# CONECTORES.net
KiCad netlist of a schematic drawn in Altium Designer
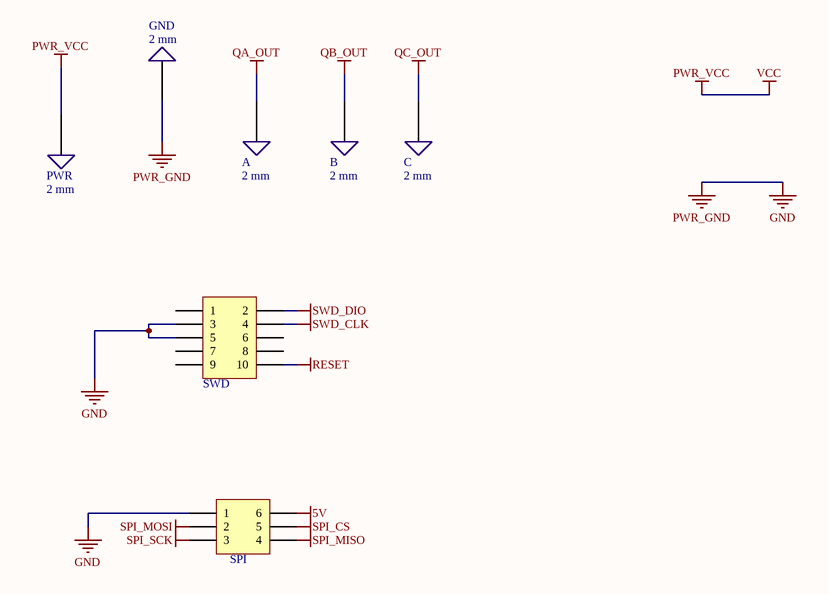
[diagram p0: CONECTORES.SchDoc]

(export (version "E")
  (design (tool "Eeschema 10.0.6"))
  (components
    (comp (ref "A")
      (value "2 mm")
      (footprint "HOLE_2mm")
      (description "Pad to solder wire")
      (libsource (lib "Connector#csv") (part "SOLDERED_WIRE_2mm"))
    )
    (comp (ref "B")
      (value "2 mm")
      (footprint "HOLE_2mm")
      (description "Pad to solder wire")
      (libsource (lib "Connector#csv") (part "SOLDERED_WIRE_2mm"))
    )
    (comp (ref "C")
      (value "2 mm")
      (footprint "HOLE_2mm")
      (description "Pad to solder wire")
      (libsource (lib "Connector#csv") (part "SOLDERED_WIRE_2mm"))
    )
    (comp (ref "GND")
      (value "2 mm")
      (footprint "HOLE_2mm")
      (description "Pad to solder wire")
      (libsource (lib "Connector#csv") (part "SOLDERED_WIRE_2mm"))
    )
    (comp (ref "PWR")
      (value "2 mm")
      (footprint "HOLE_2mm")
      (description "Pad to solder wire")
      (libsource (lib "Connector#csv") (part "SOLDERED_WIRE_2mm"))
    )
    (comp (ref "SPI")
      (value "Header 3X2")
      (footprint "Pines 2X3")
      (description "Header, 3-Pin, Dual row")
      (fields (field (name "PUBLISHER") "Altium Limited"))
      (libsource (lib "ConnectorsGordo") (part "Header 3X2"))
    )
    (comp (ref "SWD")
      (value "HEADER-5x2S")
      (footprint "G-HEADER_5x2I.05P_SM")
      (description "CONN HEADER 10POS DL UNSHRD SMD")
      (libsource (lib "Connector#csv") (part "HEADER_5x2_50mil_U"))
    )
  )
  (nets
    (net (code "1") (name "5V") (class "Default")
      (node (ref "SPI") (pin "6") (pinfunction "6_6") (pintype "passive"))
    )
    (net (code "2") (name "GND") (class "Default")
      (node (ref "GND") (pin "1") (pinfunction "Wire_1") (pintype "passive"))
      (node (ref "SPI") (pin "1") (pinfunction "1_1") (pintype "passive"))
      (node (ref "SWD") (pin "3") (pinfunction "3_3") (pintype "passive"))
      (node (ref "SWD") (pin "5") (pinfunction "5_5") (pintype "passive"))
    )
    (net (code "3") (name "PWR_VCC") (class "Default")
      (node (ref "PWR") (pin "1") (pinfunction "Wire_1") (pintype "passive"))
    )
    (net (code "4") (name "QA_OUT") (class "Default")
      (node (ref "A") (pin "1") (pinfunction "Wire_1") (pintype "passive"))
    )
    (net (code "5") (name "QB_OUT") (class "Default")
      (node (ref "B") (pin "1") (pinfunction "Wire_1") (pintype "passive"))
    )
    (net (code "6") (name "QC_OUT") (class "Default")
      (node (ref "C") (pin "1") (pinfunction "Wire_1") (pintype "passive"))
    )
    (net (code "7") (name "RESET") (class "Default")
      (node (ref "SWD") (pin "10") (pinfunction "10_10") (pintype "passive"))
    )
    (net (code "8") (name "SPI_CS") (class "Default")
      (node (ref "SPI") (pin "5") (pinfunction "5_5") (pintype "passive"))
    )
    (net (code "9") (name "SPI_MISO") (class "Default")
      (node (ref "SPI") (pin "4") (pinfunction "4_4") (pintype "passive"))
    )
    (net (code "10") (name "SPI_MOSI") (class "Default")
      (node (ref "SPI") (pin "2") (pinfunction "2_2") (pintype "passive"))
    )
    (net (code "11") (name "SPI_SCK") (class "Default")
      (node (ref "SPI") (pin "3") (pinfunction "3_3") (pintype "passive"))
    )
    (net (code "12") (name "SWD_CLK") (class "Default")
      (node (ref "SWD") (pin "4") (pinfunction "4_4") (pintype "passive"))
    )
    (net (code "13") (name "SWD_DIO") (class "Default")
      (node (ref "SWD") (pin "2") (pinfunction "2_2") (pintype "passive"))
    )
    (net (code "14") (name "unconnected-(SWD-Pad1)") (class "Default")
      (node (ref "SWD") (pin "1") (pinfunction "1_1") (pintype "passive"))
    )
    (net (code "15") (name "unconnected-(SWD-Pad6)") (class "Default")
      (node (ref "SWD") (pin "6") (pinfunction "6_6") (pintype "passive"))
    )
    (net (code "16") (name "unconnected-(SWD-Pad7)") (class "Default")
      (node (ref "SWD") (pin "7") (pinfunction "7_7") (pintype "passive"))
    )
    (net (code "17") (name "unconnected-(SWD-Pad8)") (class "Default")
      (node (ref "SWD") (pin "8") (pinfunction "8_8") (pintype "passive"))
    )
    (net (code "18") (name "unconnected-(SWD-Pad9)") (class "Default")
      (node (ref "SWD") (pin "9") (pinfunction "9_9") (pintype "passive"))
    )
  )
)
